# Power_management.net
KiCad netlist of a schematic drawn in Altium Designer
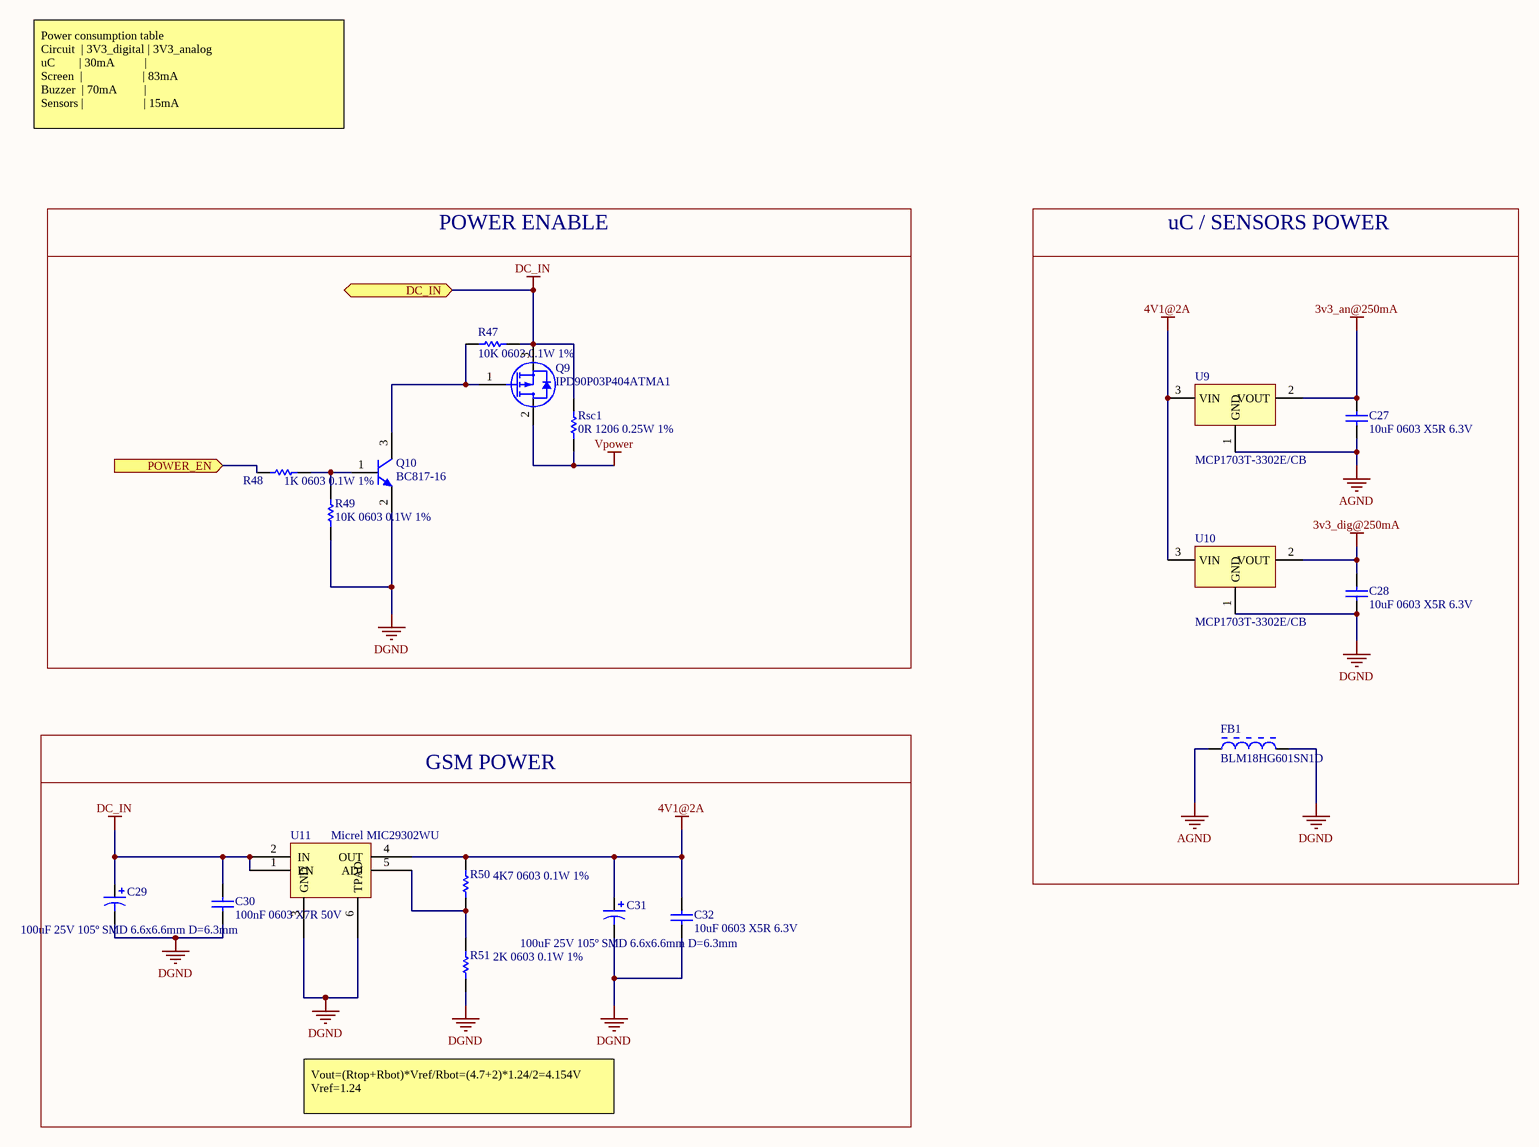
[diagram p0: Power_management.SchDoc]

(export (version "E")
  (design (tool "Eeschema 10.0.6"))
  (components
    (comp (ref "C27")
      (value "10uF 0603 X5R 6.3V")
      (footprint "CAPC1608X60X35NL10T15")
      (libsource (lib "CommunityVault") (part "CMP-121364-8"))
    )
    (comp (ref "C28")
      (value "10uF 0603 X5R 6.3V")
      (footprint "CAPC1608X60X35NL10T15")
      (libsource (lib "CommunityVault") (part "CMP-121364-8"))
    )
    (comp (ref "C29")
      (value "100uF 25V 105º SMD 6.6x6.6mm D=6.3mm")
      (footprint "PCB-5eg0a5nygcrzw5ibm1j9-1")
      (fields (field (name "MANUFACTURER PART NUMBER") "VZL101M1ETR-0607") (field (name "TOLERANCE") "20%"))
      (libsource (lib "CommunityVault") (part "CMP-a6d16ad512617916-1"))
    )
    (comp (ref "C30")
      (value "100nF 0603 X7R 50V")
      (footprint "CAPC1608X60X35NL10T15")
      (description "100nF 0603 X7R 25V")
      (libsource (lib "CommunityVault") (part "CMP-c41a0d2b65641bdd-3"))
    )
    (comp (ref "C31")
      (value "100uF 25V 105º SMD 6.6x6.6mm D=6.3mm")
      (footprint "PCB-5eg0a5nygcrzw5ibm1j9-1")
      (fields (field (name "MANUFACTURER PART NUMBER") "VZL101M1ETR-0607") (field (name "TOLERANCE") "20%"))
      (libsource (lib "CommunityVault") (part "CMP-a6d16ad512617916-1"))
    )
    (comp (ref "C32")
      (value "10uF 0603 X5R 6.3V")
      (footprint "CAPC1608X60X35NL10T15")
      (libsource (lib "CommunityVault") (part "CMP-121364-8"))
    )
    (comp (ref "FB1")
      (value "BLM18HG601SN1D")
      (footprint "MURA-BLM18-F-H1-CHIP-2_V")
      (libsource (lib "CommunityVault") (part "CMP-19299602-3"))
    )
    (comp (ref "Q9")
      (value "IPD90P03P404ATMA1")
      (footprint "DPAK IPD90P03P404ATMA1")
      (description "Single P-Channel 30 V 4.5 mOhm 100 nC OptiMOS Power Mosfet - TO-252-3-11")
      (libsource (lib "CommunityVault") (part "CMP-3103264-6"))
    )
    (comp (ref "Q10")
      (value "BC817-16")
      (footprint "PCB-856332-1")
      (description "TRANS NPN 45V 500mA SMD SOT23-3")
      (libsource (lib "CommunityVault") (part "CMP-856332-3"))
    )
    (comp (ref "R47")
      (value "10K 0603 0.1W 1%")
      (footprint "RESC1609X55X30ML10T20")
      (fields (field (name "TOLERANCE") "1%"))
      (libsource (lib "CommunityVault") (part "CMP-4716590-9"))
    )
    (comp (ref "R48")
      (value "1K 0603 0.1W 1%")
      (footprint "RESC1609X55X30ML10T20")
      (fields (field (name "MANUFACTURER PART NUMBER") "CR0603-FX-1001ELF"))
      (libsource (lib "CommunityVault") (part "CMP-a61f6f36030f79d8-4"))
    )
    (comp (ref "R49")
      (value "10K 0603 0.1W 1%")
      (footprint "RESC1609X55X30ML10T20")
      (fields (field (name "TOLERANCE") "1%"))
      (libsource (lib "CommunityVault") (part "CMP-4716590-9"))
    )
    (comp (ref "R50")
      (value "4K7 0603 0.1W 1%")
      (footprint "RESC1609X55X30ML10T20")
      (fields (field (name "TOLERANCE") "1%"))
      (libsource (lib "CommunityVault") (part "CMP-3655986-6"))
    )
    (comp (ref "R51")
      (value "2K 0603 0.1W 1%")
      (footprint "RESC1609X55X30ML10T20")
      (fields (field (name "TOLERANCE") "1%"))
      (libsource (lib "CommunityVault") (part "CMP-3655986-6"))
    )
    (comp (ref "Rsc1")
      (value "0R 1206 0.25W 1%")
      (footprint "PCB-sxvxwfnl72ysl1kmtzgv-1")
      (fields (field (name "MANUFACTURER PART NUMBER") "RC1206JR-070RL"))
      (libsource (lib "CommunityVault") (part "CMP-3f1bf473a47ce0dc-5"))
    )
    (comp (ref "U9")
      (value "MCP1703T-3302E/CB")
      (footprint "SOT-23A-CB3_L")
      (libsource (lib "CommunityVault") (part "CMP-1493313-4"))
    )
    (comp (ref "U10")
      (value "MCP1703T-3302E/CB")
      (footprint "SOT-23A-CB3_L")
      (libsource (lib "CommunityVault") (part "CMP-1493313-4"))
    )
    (comp (ref "U11")
      (value "Micrel MIC29302WU")
      (footprint "TI-KTT5_N")
      (description "MIC29302 Series 3 A 1.24 to 26 V ADJ Output Voltage LDO Regulator - TO-263-5")
      (libsource (lib "CommunityVault") (part "SYM--116"))
    )
  )
  (nets
    (net (code "1") (name "/POWER_EN") (class "Default")
      (node (ref "R48") (pin "1") (pinfunction "1_1") (pintype "passive"))
    )
    (net (code "2") (name "3v3_an@250mA") (class "Default")
      (node (ref "C27") (pin "2") (pinfunction "2_2") (pintype "passive"))
      (node (ref "U9") (pin "2") (pinfunction "VOUT_2") (pintype "power_in"))
    )
    (net (code "3") (name "3v3_dig@250mA") (class "Default")
      (node (ref "C28") (pin "2") (pinfunction "2_2") (pintype "passive"))
      (node (ref "U10") (pin "2") (pinfunction "VOUT_2") (pintype "power_in"))
    )
    (net (code "4") (name "4V1@2A") (class "Default")
      (node (ref "C31") (pin "1") (pinfunction "1_1") (pintype "passive"))
      (node (ref "C32") (pin "2") (pinfunction "2_2") (pintype "passive"))
      (node (ref "R50") (pin "2") (pinfunction "2_2") (pintype "passive"))
      (node (ref "U10") (pin "3") (pinfunction "VIN_3") (pintype "power_in"))
      (node (ref "U11") (pin "4") (pinfunction "OUT_4") (pintype "passive"))
      (node (ref "U9") (pin "3") (pinfunction "VIN_3") (pintype "power_in"))
    )
    (net (code "5") (name "AGND") (class "Default")
      (node (ref "C27") (pin "1") (pinfunction "1_1") (pintype "passive"))
      (node (ref "FB1") (pin "1") (pinfunction "1_1") (pintype "passive"))
      (node (ref "U9") (pin "1") (pinfunction "GND_1") (pintype "power_in"))
    )
    (net (code "6") (name "DC_IN") (class "Default")
      (node (ref "C29") (pin "1") (pinfunction "1_1") (pintype "passive"))
      (node (ref "C30") (pin "2") (pinfunction "2_2") (pintype "passive"))
      (node (ref "Q9") (pin "3") (pinfunction "S_3") (pintype "passive"))
      (node (ref "R47") (pin "2") (pinfunction "2_2") (pintype "passive"))
      (node (ref "Rsc1") (pin "2") (pinfunction "2_2") (pintype "passive"))
      (node (ref "U11") (pin "1") (pinfunction "EN_1") (pintype "passive"))
      (node (ref "U11") (pin "2") (pinfunction "IN_2") (pintype "passive"))
    )
    (net (code "7") (name "DGND") (class "Default")
      (node (ref "C28") (pin "1") (pinfunction "1_1") (pintype "passive"))
      (node (ref "C29") (pin "2") (pinfunction "2_2") (pintype "passive"))
      (node (ref "C30") (pin "1") (pinfunction "1_1") (pintype "passive"))
      (node (ref "C31") (pin "2") (pinfunction "2_2") (pintype "passive"))
      (node (ref "C32") (pin "1") (pinfunction "1_1") (pintype "passive"))
      (node (ref "FB1") (pin "2") (pinfunction "2_2") (pintype "passive"))
      (node (ref "Q10") (pin "2") (pinfunction "E_2") (pintype "passive"))
      (node (ref "R49") (pin "2") (pinfunction "2_2") (pintype "passive"))
      (node (ref "R51") (pin "1") (pinfunction "1_1") (pintype "passive"))
      (node (ref "U10") (pin "1") (pinfunction "GND_1") (pintype "power_in"))
      (node (ref "U11") (pin "3") (pinfunction "GND_3") (pintype "passive"))
      (node (ref "U11") (pin "6") (pinfunction "TPAD_6") (pintype "passive"))
    )
    (net (code "8") (name "Net-(Q10-B)") (class "Default")
      (node (ref "Q10") (pin "1") (pinfunction "B_1") (pintype "passive"))
      (node (ref "R48") (pin "2") (pinfunction "2_2") (pintype "passive"))
      (node (ref "R49") (pin "1") (pinfunction "1_1") (pintype "passive"))
    )
    (net (code "9") (name "Net-(Q10-C)") (class "Default")
      (node (ref "Q10") (pin "3") (pinfunction "C_3") (pintype "passive"))
      (node (ref "Q9") (pin "1") (pinfunction "G_1") (pintype "passive"))
      (node (ref "R47") (pin "1") (pinfunction "1_1") (pintype "passive"))
    )
    (net (code "10") (name "Net-(U11-ADJ)") (class "Default")
      (node (ref "R50") (pin "1") (pinfunction "1_1") (pintype "passive"))
      (node (ref "R51") (pin "2") (pinfunction "2_2") (pintype "passive"))
      (node (ref "U11") (pin "5") (pinfunction "ADJ_5") (pintype "passive"))
    )
    (net (code "11") (name "Vpower") (class "Default")
      (node (ref "Q9") (pin "2") (pinfunction "D_2") (pintype "passive"))
      (node (ref "Rsc1") (pin "1") (pinfunction "1_1") (pintype "passive"))
    )
  )
)
